# ioboard.net
KiCad netlist of a schematic drawn in EAGLE
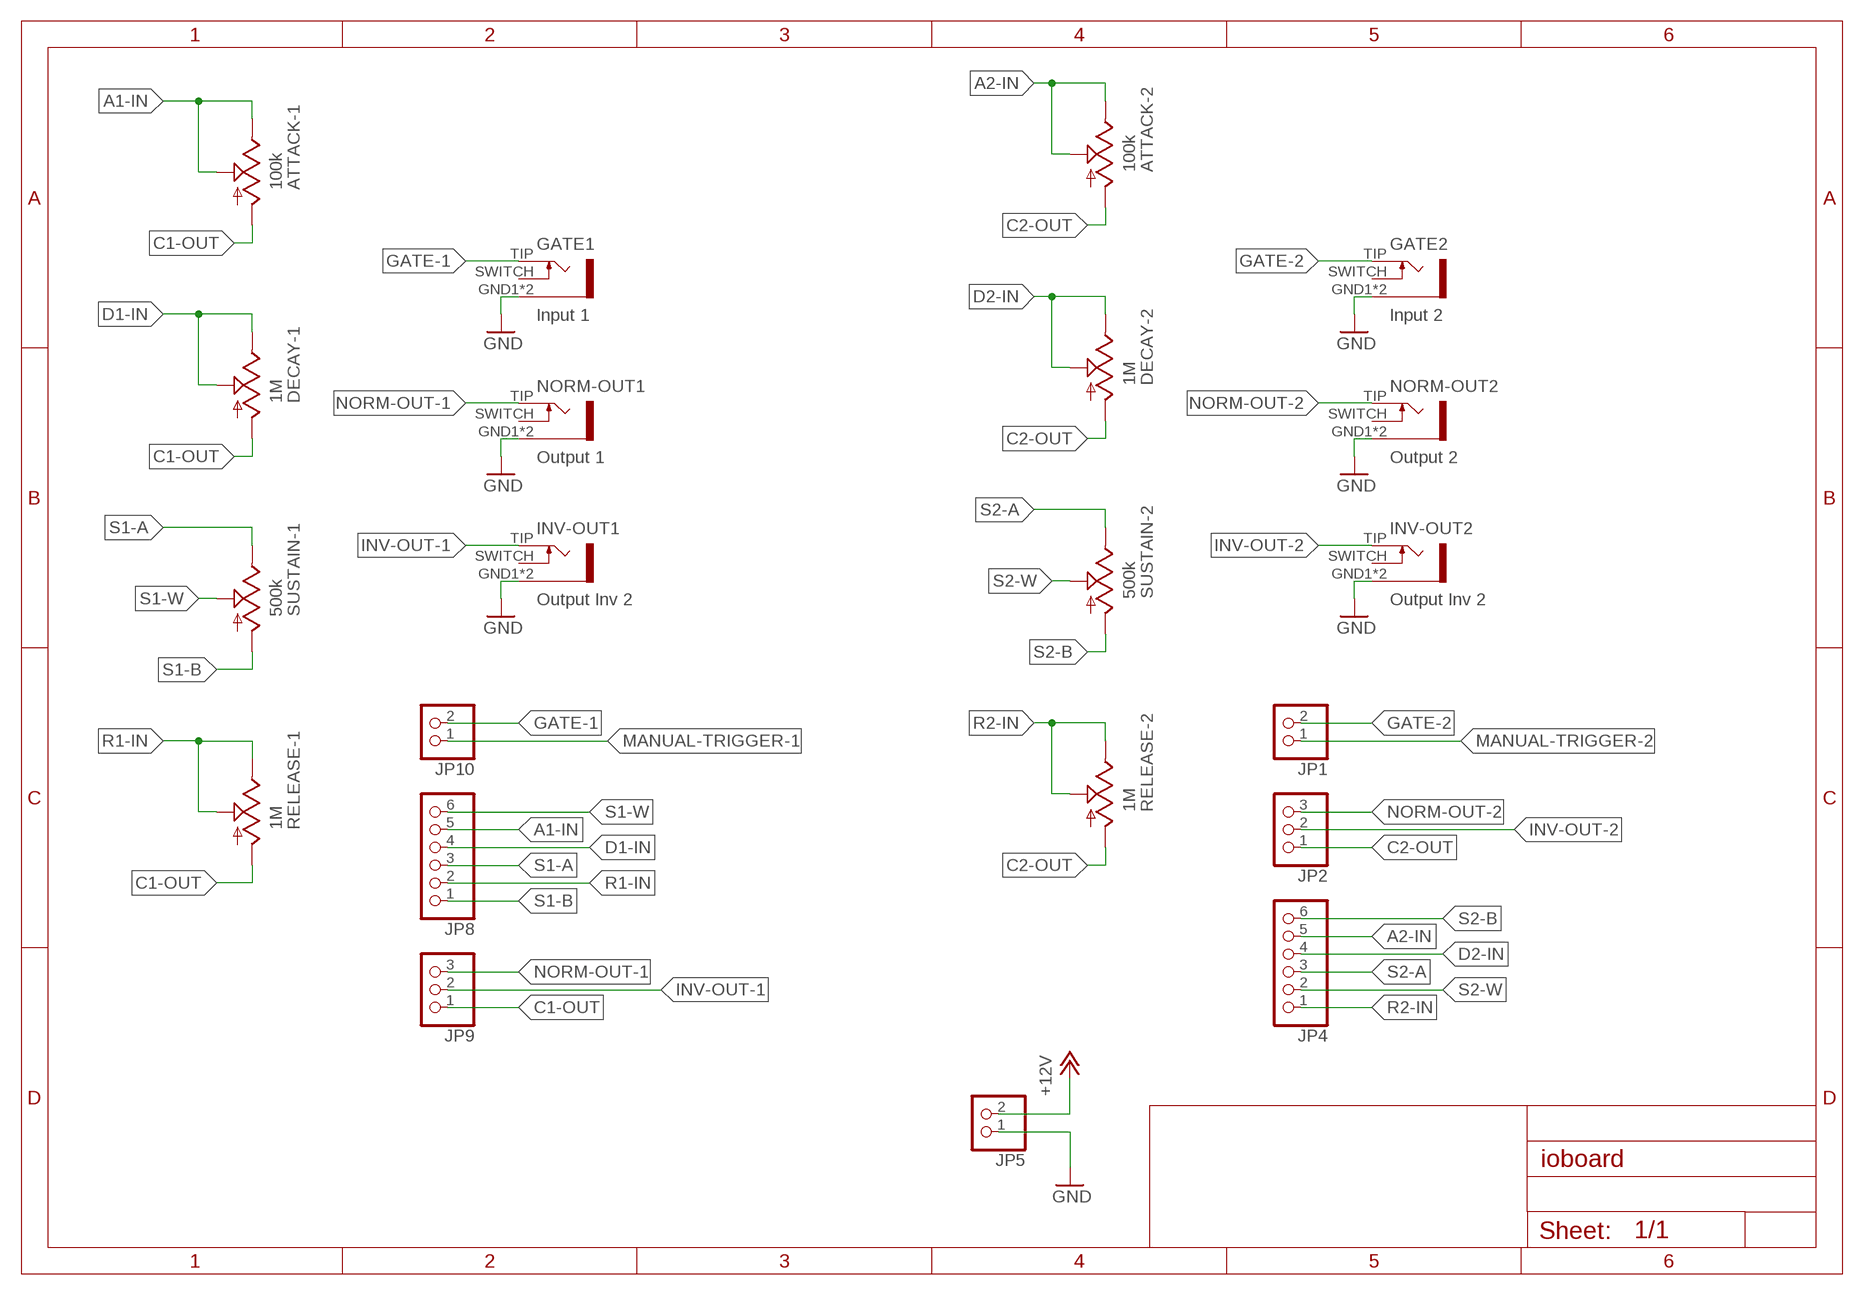
[diagram p0: schematic, sheet 1]

(export (version "E")
  (design (tool "Eeschema 10.0.6"))
  (components
    (comp (ref "ATTACK-1")
      (value "100k")
      (footprint "eagle-import:EVUF")
      (libsource (lib "eagle-import") (part "ALPHA-9MMA"))
    )
    (comp (ref "ATTACK-2")
      (value "100k")
      (footprint "eagle-import:EVUF")
      (libsource (lib "eagle-import") (part "ALPHA-9MMA"))
    )
    (comp (ref "DECAY-1")
      (value "1M")
      (footprint "eagle-import:EVUF")
      (libsource (lib "eagle-import") (part "ALPHA-9MMA"))
    )
    (comp (ref "DECAY-2")
      (value "1M")
      (footprint "eagle-import:EVUF")
      (libsource (lib "eagle-import") (part "ALPHA-9MMA"))
    )
    (comp (ref "GATE1")
      (value "Input 1")
      (footprint "eagle-import:PJ301BM")
      (libsource (lib "eagle-import") (part "PJ301BMPJ301BM"))
    )
    (comp (ref "GATE2")
      (value "Input 2")
      (footprint "eagle-import:PJ301BM")
      (libsource (lib "eagle-import") (part "PJ301BMPJ301BM"))
    )
    (comp (ref "INV-OUT1")
      (value "Output Inv 2")
      (footprint "eagle-import:PJ301BM")
      (libsource (lib "eagle-import") (part "PJ301BMPJ301BM"))
    )
    (comp (ref "INV-OUT2")
      (value "Output Inv 2")
      (footprint "eagle-import:PJ301BM")
      (libsource (lib "eagle-import") (part "PJ301BMPJ301BM"))
    )
    (comp (ref "JP1")
      (value "PINHD-1X2")
      (footprint "eagle-import:1X02")
      (libsource (lib "eagle-import") (part "PINHD-1X2"))
    )
    (comp (ref "JP2")
      (value "PINHD-1X3")
      (footprint "eagle-import:1X03")
      (libsource (lib "eagle-import") (part "PINHD-1X3"))
    )
    (comp (ref "JP4")
      (value "PINHD-1X6")
      (footprint "eagle-import:1X06")
      (libsource (lib "eagle-import") (part "PINHD-1X6"))
    )
    (comp (ref "JP5")
      (value "PINHD-1X2")
      (footprint "eagle-import:1X02")
      (libsource (lib "eagle-import") (part "PINHD-1X2"))
    )
    (comp (ref "JP8")
      (value "PINHD-1X6")
      (footprint "eagle-import:1X06")
      (libsource (lib "eagle-import") (part "PINHD-1X6"))
    )
    (comp (ref "JP9")
      (value "PINHD-1X3")
      (footprint "eagle-import:1X03")
      (libsource (lib "eagle-import") (part "PINHD-1X3"))
    )
    (comp (ref "JP10")
      (value "PINHD-1X2")
      (footprint "eagle-import:1X02")
      (libsource (lib "eagle-import") (part "PINHD-1X2"))
    )
    (comp (ref "NORM-OUT1")
      (value "Output 1")
      (footprint "eagle-import:PJ301BM")
      (libsource (lib "eagle-import") (part "PJ301BMPJ301BM"))
    )
    (comp (ref "NORM-OUT2")
      (value "Output 2")
      (footprint "eagle-import:PJ301BM")
      (libsource (lib "eagle-import") (part "PJ301BMPJ301BM"))
    )
    (comp (ref "RELEASE-1")
      (value "1M")
      (footprint "eagle-import:EVUF")
      (libsource (lib "eagle-import") (part "ALPHA-9MMA"))
    )
    (comp (ref "RELEASE-2")
      (value "1M")
      (footprint "eagle-import:EVUF")
      (libsource (lib "eagle-import") (part "ALPHA-9MMA"))
    )
    (comp (ref "SUSTAIN-1")
      (value "500k")
      (footprint "eagle-import:EVUF")
      (libsource (lib "eagle-import") (part "ALPHA-9MMA"))
    )
    (comp (ref "SUSTAIN-2")
      (value "500k")
      (footprint "eagle-import:EVUF")
      (libsource (lib "eagle-import") (part "ALPHA-9MMA"))
    )
  )
  (nets
    (net (code "1") (name "+12V") (class "Default")
      (node (ref "JP5") (pin "2") (pinfunction "2_2") (pintype "passive"))
    )
    (net (code "2") (name "A1-IN") (class "Default")
      (node (ref "ATTACK-1") (pin "2") (pinfunction "S_2") (pintype "passive"))
      (node (ref "ATTACK-1") (pin "3") (pinfunction "E_3") (pintype "passive"))
      (node (ref "JP8") (pin "5") (pinfunction "5_5") (pintype "passive"))
    )
    (net (code "3") (name "A2-IN") (class "Default")
      (node (ref "ATTACK-2") (pin "2") (pinfunction "S_2") (pintype "passive"))
      (node (ref "ATTACK-2") (pin "3") (pinfunction "E_3") (pintype "passive"))
      (node (ref "JP4") (pin "5") (pinfunction "5_5") (pintype "passive"))
    )
    (net (code "4") (name "C1-OUT") (class "Default")
      (node (ref "ATTACK-1") (pin "1") (pinfunction "A_1") (pintype "passive"))
      (node (ref "DECAY-1") (pin "1") (pinfunction "A_1") (pintype "passive"))
      (node (ref "JP9") (pin "1") (pinfunction "1_1") (pintype "passive"))
      (node (ref "RELEASE-1") (pin "1") (pinfunction "A_1") (pintype "passive"))
    )
    (net (code "5") (name "C2-OUT") (class "Default")
      (node (ref "ATTACK-2") (pin "1") (pinfunction "A_1") (pintype "passive"))
      (node (ref "DECAY-2") (pin "1") (pinfunction "A_1") (pintype "passive"))
      (node (ref "JP2") (pin "1") (pinfunction "1_1") (pintype "passive"))
      (node (ref "RELEASE-2") (pin "1") (pinfunction "A_1") (pintype "passive"))
    )
    (net (code "6") (name "D1-IN") (class "Default")
      (node (ref "DECAY-1") (pin "2") (pinfunction "S_2") (pintype "passive"))
      (node (ref "DECAY-1") (pin "3") (pinfunction "E_3") (pintype "passive"))
      (node (ref "JP8") (pin "4") (pinfunction "4_4") (pintype "passive"))
    )
    (net (code "7") (name "D2-IN") (class "Default")
      (node (ref "DECAY-2") (pin "2") (pinfunction "S_2") (pintype "passive"))
      (node (ref "DECAY-2") (pin "3") (pinfunction "E_3") (pintype "passive"))
      (node (ref "JP4") (pin "4") (pinfunction "4_4") (pintype "passive"))
    )
    (net (code "8") (name "GATE-1") (class "Default")
      (node (ref "GATE1") (pin "TIP") (pinfunction "3_TIP") (pintype "passive"))
      (node (ref "JP10") (pin "2") (pinfunction "2_2") (pintype "passive"))
    )
    (net (code "9") (name "GATE-2") (class "Default")
      (node (ref "GATE2") (pin "TIP") (pinfunction "3_TIP") (pintype "passive"))
      (node (ref "JP1") (pin "2") (pinfunction "2_2") (pintype "passive"))
    )
    (net (code "10") (name "GND") (class "Default")
      (node (ref "GATE1") (pin "GND1") (pinfunction "5_GND1") (pintype "passive"))
      (node (ref "GATE1") (pin "GND2") (pinfunction "5_GND2") (pintype "passive"))
      (node (ref "GATE2") (pin "GND1") (pinfunction "5_GND1") (pintype "passive"))
      (node (ref "GATE2") (pin "GND2") (pinfunction "5_GND2") (pintype "passive"))
      (node (ref "INV-OUT1") (pin "GND1") (pinfunction "5_GND1") (pintype "passive"))
      (node (ref "INV-OUT1") (pin "GND2") (pinfunction "5_GND2") (pintype "passive"))
      (node (ref "INV-OUT2") (pin "GND1") (pinfunction "5_GND1") (pintype "passive"))
      (node (ref "INV-OUT2") (pin "GND2") (pinfunction "5_GND2") (pintype "passive"))
      (node (ref "JP5") (pin "1") (pinfunction "1_1") (pintype "passive"))
      (node (ref "NORM-OUT1") (pin "GND1") (pinfunction "5_GND1") (pintype "passive"))
      (node (ref "NORM-OUT1") (pin "GND2") (pinfunction "5_GND2") (pintype "passive"))
      (node (ref "NORM-OUT2") (pin "GND1") (pinfunction "5_GND1") (pintype "passive"))
      (node (ref "NORM-OUT2") (pin "GND2") (pinfunction "5_GND2") (pintype "passive"))
    )
    (net (code "11") (name "INV-OUT-1") (class "Default")
      (node (ref "INV-OUT1") (pin "TIP") (pinfunction "3_TIP") (pintype "passive"))
      (node (ref "JP9") (pin "2") (pinfunction "2_2") (pintype "passive"))
    )
    (net (code "12") (name "INV-OUT-2") (class "Default")
      (node (ref "INV-OUT2") (pin "TIP") (pinfunction "3_TIP") (pintype "passive"))
      (node (ref "JP2") (pin "2") (pinfunction "2_2") (pintype "passive"))
    )
    (net (code "13") (name "MANUAL-TRIGGER-1") (class "Default")
      (node (ref "JP10") (pin "1") (pinfunction "1_1") (pintype "passive"))
    )
    (net (code "14") (name "MANUAL-TRIGGER-2") (class "Default")
      (node (ref "JP1") (pin "1") (pinfunction "1_1") (pintype "passive"))
    )
    (net (code "15") (name "NORM-OUT-1") (class "Default")
      (node (ref "JP9") (pin "3") (pinfunction "3_3") (pintype "passive"))
      (node (ref "NORM-OUT1") (pin "TIP") (pinfunction "3_TIP") (pintype "passive"))
    )
    (net (code "16") (name "NORM-OUT-2") (class "Default")
      (node (ref "JP2") (pin "3") (pinfunction "3_3") (pintype "passive"))
      (node (ref "NORM-OUT2") (pin "TIP") (pinfunction "3_TIP") (pintype "passive"))
    )
    (net (code "17") (name "R1-IN") (class "Default")
      (node (ref "JP8") (pin "2") (pinfunction "2_2") (pintype "passive"))
      (node (ref "RELEASE-1") (pin "2") (pinfunction "S_2") (pintype "passive"))
      (node (ref "RELEASE-1") (pin "3") (pinfunction "E_3") (pintype "passive"))
    )
    (net (code "18") (name "R2-IN") (class "Default")
      (node (ref "JP4") (pin "1") (pinfunction "1_1") (pintype "passive"))
      (node (ref "RELEASE-2") (pin "2") (pinfunction "S_2") (pintype "passive"))
      (node (ref "RELEASE-2") (pin "3") (pinfunction "E_3") (pintype "passive"))
    )
    (net (code "19") (name "S1-A") (class "Default")
      (node (ref "JP8") (pin "3") (pinfunction "3_3") (pintype "passive"))
      (node (ref "SUSTAIN-1") (pin "3") (pinfunction "E_3") (pintype "passive"))
    )
    (net (code "20") (name "S1-B") (class "Default")
      (node (ref "JP8") (pin "1") (pinfunction "1_1") (pintype "passive"))
      (node (ref "SUSTAIN-1") (pin "1") (pinfunction "A_1") (pintype "passive"))
    )
    (net (code "21") (name "S1-W") (class "Default")
      (node (ref "JP8") (pin "6") (pinfunction "6_6") (pintype "passive"))
      (node (ref "SUSTAIN-1") (pin "2") (pinfunction "S_2") (pintype "passive"))
    )
    (net (code "22") (name "S2-A") (class "Default")
      (node (ref "JP4") (pin "3") (pinfunction "3_3") (pintype "passive"))
      (node (ref "SUSTAIN-2") (pin "3") (pinfunction "E_3") (pintype "passive"))
    )
    (net (code "23") (name "S2-B") (class "Default")
      (node (ref "JP4") (pin "6") (pinfunction "6_6") (pintype "passive"))
      (node (ref "SUSTAIN-2") (pin "1") (pinfunction "A_1") (pintype "passive"))
    )
    (net (code "24") (name "S2-W") (class "Default")
      (node (ref "JP4") (pin "2") (pinfunction "2_2") (pintype "passive"))
      (node (ref "SUSTAIN-2") (pin "2") (pinfunction "S_2") (pintype "passive"))
    )
    (net (code "25") (name "unconnected-(GATE1-4-PadSWITCH)") (class "Default")
      (node (ref "GATE1") (pin "SWITCH") (pinfunction "4_SWITCH") (pintype "passive"))
    )
    (net (code "26") (name "unconnected-(GATE2-4-PadSWITCH)") (class "Default")
      (node (ref "GATE2") (pin "SWITCH") (pinfunction "4_SWITCH") (pintype "passive"))
    )
    (net (code "27") (name "unconnected-(INV-OUT1-4-PadSWITCH)") (class "Default")
      (node (ref "INV-OUT1") (pin "SWITCH") (pinfunction "4_SWITCH") (pintype "passive"))
    )
    (net (code "28") (name "unconnected-(INV-OUT2-4-PadSWITCH)") (class "Default")
      (node (ref "INV-OUT2") (pin "SWITCH") (pinfunction "4_SWITCH") (pintype "passive"))
    )
    (net (code "29") (name "unconnected-(NORM-OUT1-4-PadSWITCH)") (class "Default")
      (node (ref "NORM-OUT1") (pin "SWITCH") (pinfunction "4_SWITCH") (pintype "passive"))
    )
    (net (code "30") (name "unconnected-(NORM-OUT2-4-PadSWITCH)") (class "Default")
      (node (ref "NORM-OUT2") (pin "SWITCH") (pinfunction "4_SWITCH") (pintype "passive"))
    )
  )
)
